# vybijec.net
KiCad netlist of a schematic drawn in EAGLE
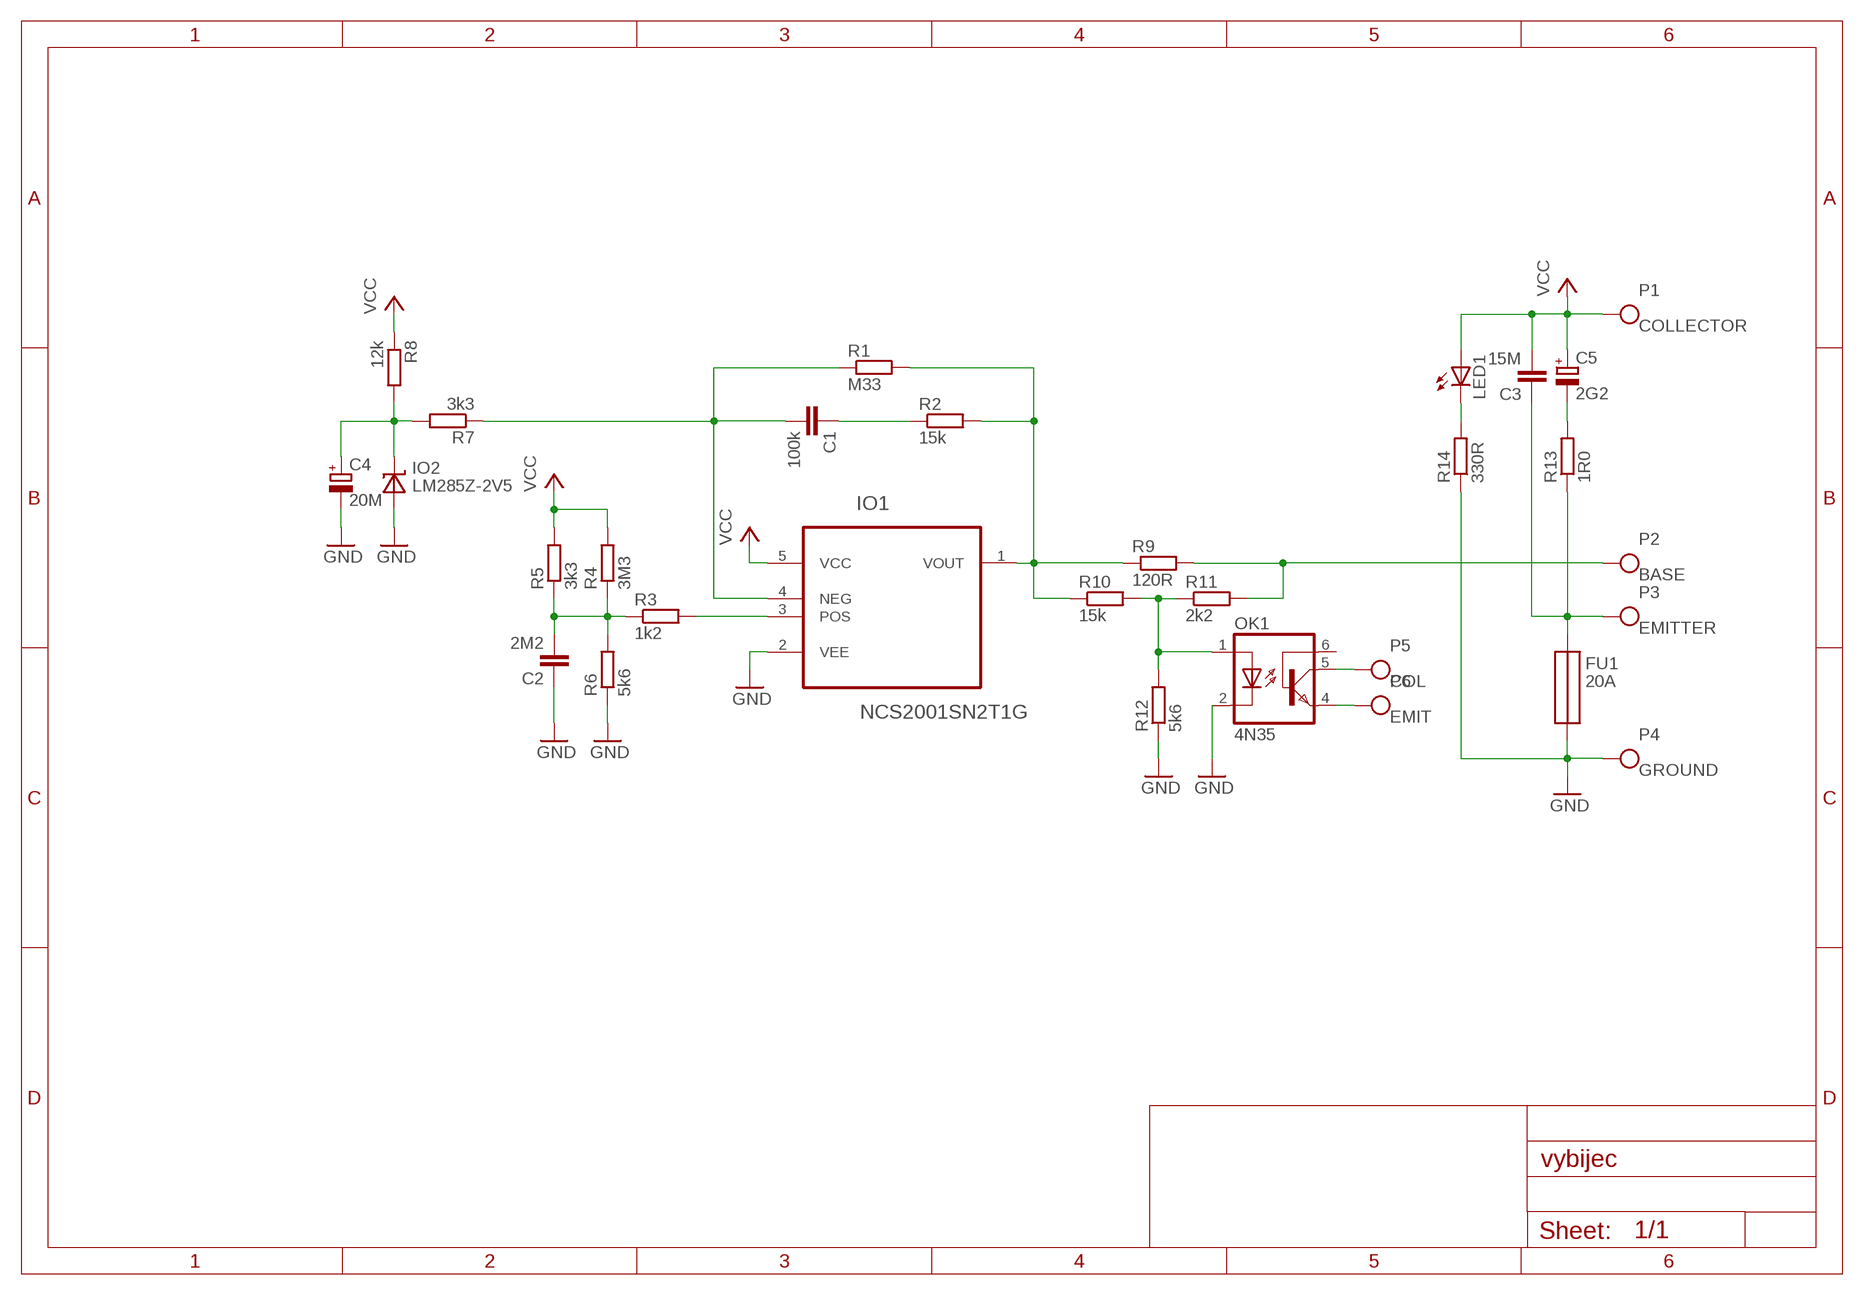
[diagram p0: schematic, sheet 1]

(export (version "E")
  (design (tool "Eeschema 10.0.6"))
  (components
    (comp (ref "C1")
      (value "100k")
      (footprint "eagle-import:C050-025X075")
      (libsource (lib "eagle-import") (part "C-EU050-025X075"))
    )
    (comp (ref "C2")
      (value "2M2")
      (footprint "eagle-import:C050-050X075")
      (libsource (lib "eagle-import") (part "C-EU050-050X075"))
    )
    (comp (ref "C3")
      (value "15M")
      (footprint "eagle-import:C050-075X075")
      (libsource (lib "eagle-import") (part "C-EU050-075X075"))
    )
    (comp (ref "C4")
      (value "20M")
      (footprint "eagle-import:E22-6")
      (libsource (lib "eagle-import") (part "CPOL-EUE22-6AXIAL"))
    )
    (comp (ref "C5")
      (value "2G2")
      (footprint "eagle-import:E5-10,5")
      (libsource (lib "eagle-import") (part "CPOL-EUE5-10.5"))
    )
    (comp (ref "FU1")
      (value "20A")
      (footprint "eagle-import:POJ20X6")
      (libsource (lib "eagle-import") (part "POJISTKA"))
    )
    (comp (ref "IO1")
      (value "NCS2001SN2T1G")
      (footprint "eagle-import:SOT95P275X110-5N")
      (libsource (lib "eagle-import") (part "NCS2001SN2T1G"))
    )
    (comp (ref "IO2")
      (value "LM285Z-2V5")
      (footprint "eagle-import:TO92-")
      (libsource (lib "eagle-import") (part "LM285Z-2V5"))
    )
    (comp (ref "LED1")
      (value "LED3MM")
      (footprint "eagle-import:LED3MM")
      (libsource (lib "eagle-import") (part "LED3MM"))
    )
    (comp (ref "OK1")
      (value "4N35")
      (footprint "eagle-import:DIL06")
      (fields (field (name "MF") "FAIRCHILD SEMICONDUCTOR"))
      (libsource (lib "eagle-import") (part "4N35"))
    )
    (comp (ref "P1")
      (value "COLLECTOR")
      (footprint "eagle-import:PAD3MM")
      (libsource (lib "eagle-import") (part "PADPAD3MM"))
    )
    (comp (ref "P2")
      (value "BASE")
      (footprint "eagle-import:PAD3MM")
      (libsource (lib "eagle-import") (part "PADPAD3MM"))
    )
    (comp (ref "P3")
      (value "EMITTER")
      (footprint "eagle-import:PAD3MM")
      (libsource (lib "eagle-import") (part "PADPAD3MM"))
    )
    (comp (ref "P4")
      (value "GROUND")
      (footprint "eagle-import:PAD3MM")
      (libsource (lib "eagle-import") (part "PADPAD3MM"))
    )
    (comp (ref "P5")
      (value "COL")
      (footprint "eagle-import:PAD1.6MM")
      (libsource (lib "eagle-import") (part "PADPAD1.6MM"))
    )
    (comp (ref "P6")
      (value "EMIT")
      (footprint "eagle-import:PAD1.6MM")
      (libsource (lib "eagle-import") (part "PADPAD1.6MM"))
    )
    (comp (ref "R1")
      (value "M33")
      (footprint "eagle-import:0207_10")
      (libsource (lib "eagle-import") (part "R-EU_0207/10"))
    )
    (comp (ref "R2")
      (value "15k")
      (footprint "eagle-import:0207_10")
      (libsource (lib "eagle-import") (part "R-EU_0207/10"))
    )
    (comp (ref "R3")
      (value "1k2")
      (footprint "eagle-import:0207_10")
      (libsource (lib "eagle-import") (part "R-EU_0207/10"))
    )
    (comp (ref "R4")
      (value "3M3")
      (footprint "eagle-import:0207_10")
      (libsource (lib "eagle-import") (part "R-EU_0207/10"))
    )
    (comp (ref "R5")
      (value "3k3")
      (footprint "eagle-import:0207_10")
      (libsource (lib "eagle-import") (part "R-EU_0207/10"))
    )
    (comp (ref "R6")
      (value "5k6")
      (footprint "eagle-import:0207_10")
      (libsource (lib "eagle-import") (part "R-EU_0207/10"))
    )
    (comp (ref "R7")
      (value "3k3")
      (footprint "eagle-import:0207_10")
      (libsource (lib "eagle-import") (part "R-EU_0207/10"))
    )
    (comp (ref "R8")
      (value "12k")
      (footprint "eagle-import:0207_10")
      (libsource (lib "eagle-import") (part "R-EU_0207/10"))
    )
    (comp (ref "R9")
      (value "120R")
      (footprint "eagle-import:0207_10")
      (libsource (lib "eagle-import") (part "R-EU_0207/10"))
    )
    (comp (ref "R10")
      (value "15k")
      (footprint "eagle-import:0207_10")
      (libsource (lib "eagle-import") (part "R-EU_0207/10"))
    )
    (comp (ref "R11")
      (value "2k2")
      (footprint "eagle-import:0207_10")
      (libsource (lib "eagle-import") (part "R-EU_0207/10"))
    )
    (comp (ref "R12")
      (value "5k6")
      (footprint "eagle-import:0207_10")
      (libsource (lib "eagle-import") (part "R-EU_0207/10"))
    )
    (comp (ref "R13")
      (value "1R0")
      (footprint "eagle-import:R1206")
      (libsource (lib "eagle-import") (part "R-EU_R1206"))
    )
    (comp (ref "R14")
      (value "330R")
      (footprint "eagle-import:0207_10")
      (libsource (lib "eagle-import") (part "R-EU_0207/10"))
    )
  )
  (nets
    (net (code "1") (name "GND") (class "Default")
      (node (ref "C2") (pin "1") (pinfunction "1_1") (pintype "passive"))
      (node (ref "C4") (pin "-") (pinfunction "-_-") (pintype "passive"))
      (node (ref "FU1") (pin "2-1") (pinfunction "P$2_2-1") (pintype "bidirectional"))
      (node (ref "FU1") (pin "2-2") (pinfunction "P$2_2-2") (pintype "bidirectional"))
      (node (ref "FU1") (pin "2-3") (pinfunction "P$2_2-3") (pintype "bidirectional"))
      (node (ref "FU1") (pin "2-4") (pinfunction "P$2_2-4") (pintype "bidirectional"))
      (node (ref "IO1") (pin "2") (pinfunction "VEE_2") (pintype "passive"))
      (node (ref "IO2") (pin "1") (pinfunction "ANODE_1") (pintype "bidirectional"))
      (node (ref "OK1") (pin "2") (pinfunction "C_2") (pintype "passive"))
      (node (ref "P4") (pin "1") (pinfunction "P$1_1") (pintype "passive"))
      (node (ref "R12") (pin "1") (pinfunction "1_1") (pintype "passive"))
      (node (ref "R14") (pin "1") (pinfunction "1_1") (pintype "passive"))
      (node (ref "R6") (pin "1") (pinfunction "1_1") (pintype "passive"))
    )
    (net (code "2") (name "Net-(C1-Pad1)") (class "Default")
      (node (ref "C1") (pin "1") (pinfunction "1_1") (pintype "passive"))
      (node (ref "R2") (pin "1") (pinfunction "1_1") (pintype "passive"))
    )
    (net (code "3") (name "Net-(C2-Pad2)") (class "Default")
      (node (ref "C2") (pin "2") (pinfunction "2_2") (pintype "passive"))
      (node (ref "R3") (pin "1") (pinfunction "1_1") (pintype "passive"))
      (node (ref "R4") (pin "1") (pinfunction "1_1") (pintype "passive"))
      (node (ref "R5") (pin "1") (pinfunction "1_1") (pintype "passive"))
      (node (ref "R6") (pin "2") (pinfunction "2_2") (pintype "passive"))
    )
    (net (code "4") (name "Net-(C5-Pad-)") (class "Default")
      (node (ref "C5") (pin "-") (pinfunction "-_-") (pintype "passive"))
      (node (ref "R13") (pin "2") (pinfunction "2_2") (pintype "passive"))
    )
    (net (code "5") (name "Net-(IO1-NEG)") (class "Default")
      (node (ref "C1") (pin "2") (pinfunction "2_2") (pintype "passive"))
      (node (ref "IO1") (pin "4") (pinfunction "NEG_4") (pintype "input"))
      (node (ref "R1") (pin "1") (pinfunction "1_1") (pintype "passive"))
      (node (ref "R7") (pin "1") (pinfunction "1_1") (pintype "passive"))
    )
    (net (code "6") (name "Net-(IO1-POS)") (class "Default")
      (node (ref "IO1") (pin "3") (pinfunction "POS_3") (pintype "input"))
      (node (ref "R3") (pin "2") (pinfunction "2_2") (pintype "passive"))
    )
    (net (code "7") (name "Net-(IO1-VOUT)") (class "Default")
      (node (ref "IO1") (pin "1") (pinfunction "VOUT_1") (pintype "output"))
      (node (ref "R1") (pin "2") (pinfunction "2_2") (pintype "passive"))
      (node (ref "R10") (pin "1") (pinfunction "1_1") (pintype "passive"))
      (node (ref "R2") (pin "2") (pinfunction "2_2") (pintype "passive"))
      (node (ref "R9") (pin "1") (pinfunction "1_1") (pintype "passive"))
    )
    (net (code "8") (name "Net-(IO2-KATODE)") (class "Default")
      (node (ref "C4") (pin "+") (pinfunction "+_+") (pintype "passive"))
      (node (ref "IO2") (pin "2") (pinfunction "KATODE_2") (pintype "bidirectional"))
      (node (ref "R7") (pin "2") (pinfunction "2_2") (pintype "passive"))
      (node (ref "R8") (pin "2") (pinfunction "2_2") (pintype "passive"))
    )
    (net (code "9") (name "Net-(LED1-C)") (class "Default")
      (node (ref "LED1") (pin "K") (pinfunction "C_K") (pintype "passive"))
      (node (ref "R14") (pin "2") (pinfunction "2_2") (pintype "passive"))
    )
    (net (code "10") (name "Net-(OK1-A)") (class "Default")
      (node (ref "OK1") (pin "1") (pinfunction "A_1") (pintype "passive"))
      (node (ref "R10") (pin "2") (pinfunction "2_2") (pintype "passive"))
      (node (ref "R11") (pin "1") (pinfunction "1_1") (pintype "passive"))
      (node (ref "R12") (pin "2") (pinfunction "2_2") (pintype "passive"))
    )
    (net (code "11") (name "Net-(OK1-COL)") (class "Default")
      (node (ref "OK1") (pin "5") (pinfunction "COL_5") (pintype "passive"))
      (node (ref "P5") (pin "P$1") (pinfunction "P$1_P$1") (pintype "passive"))
    )
    (net (code "12") (name "Net-(OK1-EMI)") (class "Default")
      (node (ref "OK1") (pin "4") (pinfunction "EMI_4") (pintype "passive"))
      (node (ref "P6") (pin "P$1") (pinfunction "P$1_P$1") (pintype "passive"))
    )
    (net (code "13") (name "Net-(P2-P$1)") (class "Default")
      (node (ref "P2") (pin "1") (pinfunction "P$1_1") (pintype "passive"))
      (node (ref "R11") (pin "2") (pinfunction "2_2") (pintype "passive"))
      (node (ref "R9") (pin "2") (pinfunction "2_2") (pintype "passive"))
    )
    (net (code "14") (name "Net-(P3-P$1)") (class "Default")
      (node (ref "C3") (pin "1") (pinfunction "1_1") (pintype "passive"))
      (node (ref "FU1") (pin "1-1") (pinfunction "P$1_1-1") (pintype "bidirectional"))
      (node (ref "FU1") (pin "1-2") (pinfunction "P$1_1-2") (pintype "bidirectional"))
      (node (ref "FU1") (pin "1-3") (pinfunction "P$1_1-3") (pintype "bidirectional"))
      (node (ref "FU1") (pin "1-4") (pinfunction "P$1_1-4") (pintype "bidirectional"))
      (node (ref "P3") (pin "1") (pinfunction "P$1_1") (pintype "passive"))
      (node (ref "R13") (pin "1") (pinfunction "1_1") (pintype "passive"))
    )
    (net (code "15") (name "VCC") (class "Default")
      (node (ref "C3") (pin "2") (pinfunction "2_2") (pintype "passive"))
      (node (ref "C5") (pin "+") (pinfunction "+_+") (pintype "passive"))
      (node (ref "IO1") (pin "5") (pinfunction "VCC_5") (pintype "power_in"))
      (node (ref "LED1") (pin "A") (pinfunction "A_A") (pintype "passive"))
      (node (ref "P1") (pin "1") (pinfunction "P$1_1") (pintype "passive"))
      (node (ref "R4") (pin "2") (pinfunction "2_2") (pintype "passive"))
      (node (ref "R5") (pin "2") (pinfunction "2_2") (pintype "passive"))
      (node (ref "R8") (pin "1") (pinfunction "1_1") (pintype "passive"))
    )
    (net (code "16") (name "unconnected-(OK1-BAS-Pad6)") (class "Default")
      (node (ref "OK1") (pin "6") (pinfunction "BAS_6") (pintype "passive"))
    )
  )
)
